# Ease_buck_regulator_v2.net
KiCad netlist of a schematic drawn in EasyEDA Pro
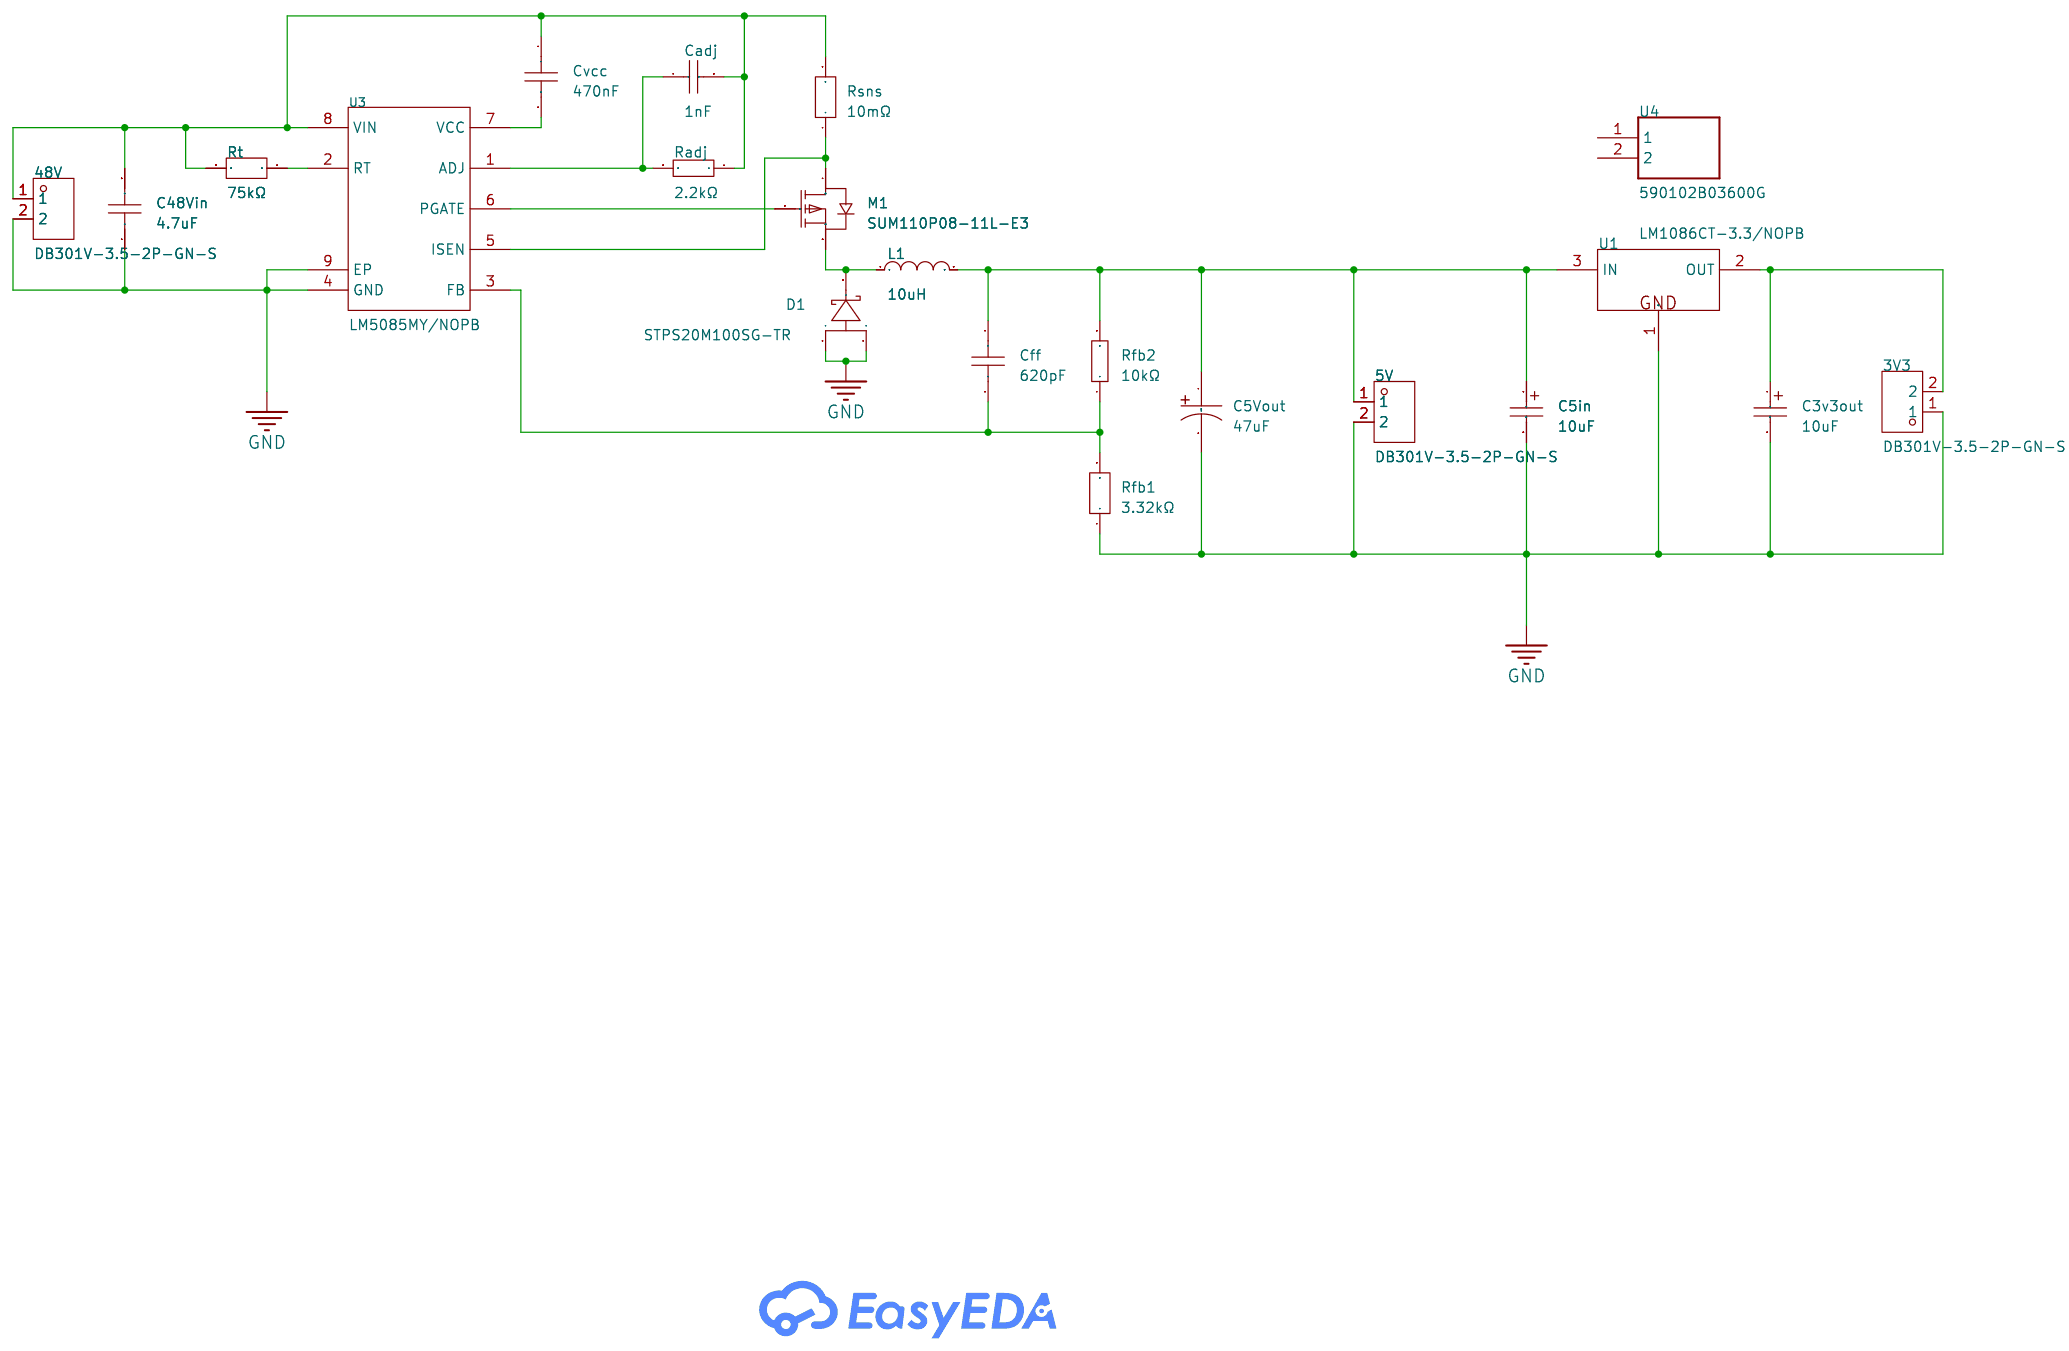
[diagram p0: schematic sheet]

(export (version "E")
  (design (tool "Eeschema 10.0.6"))
  (components
    (comp (ref "3V3")
      (value "DB301V-3.5-2P-GN-S")
      (footprint "easyedapro:CONN-TH_DB301V-3.5-2P-GN")
      (fields (field (name "Manufacturer") "DORABO(地博电气)"))
      (libsource (lib "easyedapro") (part "DB301V-3.5-2P-GN"))
    )
    (comp (ref "5V")
      (value "DB301V-3.5-2P-GN-S")
      (footprint "easyedapro:CONN-TH_DB301V-3.5-2P-GN")
      (fields (field (name "Manufacturer") "DORABO(地博电气)"))
      (libsource (lib "easyedapro") (part "DB301V-3.5-2P-GN"))
    )
    (comp (ref "48V")
      (value "DB301V-3.5-2P-GN-S")
      (footprint "easyedapro:CONN-TH_DB301V-3.5-2P-GN")
      (fields (field (name "Manufacturer") "DORABO(地博电气)"))
      (libsource (lib "easyedapro") (part "DB301V-3.5-2P-GN"))
    )
    (comp (ref "C3v3out")
      (value "10uF")
      (footprint "easyedapro:CASE-A_3216")
      (fields (field (name "Manufacturer Part") "TAJA106M010RNJ") (field (name "Manufacturer") "Kyocera AVX"))
      (libsource (lib "easyedapro") (part "TAJA106M010RNJ"))
    )
    (comp (ref "C5in")
      (value "10uF")
      (footprint "easyedapro:CASE-A_3216")
      (fields (field (name "Manufacturer Part") "TAJA106M010RNJ") (field (name "Manufacturer") "Kyocera AVX"))
      (libsource (lib "easyedapro") (part "TAJA106M010RNJ"))
    )
    (comp (ref "C5Vout")
      (value "47uF")
      (footprint "easyedapro:CAP-SMD_L3.5-W2.8")
      (fields
        (field (name "Manufacturer Part") "TPSB476K010R0250")
        (field (name "Manufacturer") "Kyocera AVX")
      )
      (libsource (lib "easyedapro") (part "TPSB476K010R0250"))
    )
    (comp (ref "C48Vin")
      (value "4.7uF")
      (footprint "easyedapro:C1210")
      (description "Capacitance:4.7uF Tolerance:±10% Tolerance:±10% Voltage Rating:100V Temperature Coefficient:X7S")
      (fields
        (field (name "Manufacturer Part") "GCM32DC72A475KE02L")
        (field (name "Manufacturer") "muRata(村田)")
      )
      (libsource (lib "easyedapro") (part "GCM32DC72A475KE02L"))
    )
    (comp (ref "Cadj")
      (value "1nF")
      (footprint "easyedapro:C0805")
      (description "Capacitance:1nF Tolerance:±5% Tolerance:±5% Voltage Rating:50V Temperature Coefficient:C0G")
      (fields
        (field (name "Manufacturer Part") "CL21C102JBCNNNC")
        (field (name "Manufacturer") "SAMSUNG(三星)")
      )
      (libsource (lib "easyedapro") (part "CL21C102JBCNNNC"))
    )
    (comp (ref "Cff")
      (value "620pF")
      (footprint "easyedapro:C0805")
      (fields
        (field (name "Manufacturer Part") "CL21C621JBCNNNC")
        (field (name "Manufacturer") "SAMSUNG(三星)")
      )
      (libsource (lib "easyedapro") (part "CL21C621JBCNNNC"))
    )
    (comp (ref "Cvcc")
      (value "470nF")
      (footprint "easyedapro:C0805")
      (fields
        (field (name "Manufacturer Part") "TMK212BJ474KD-T")
        (field (name "Manufacturer") "TAIYO YUDEN(太诱)")
      )
      (libsource (lib "easyedapro") (part "TMK212BJ474KD-T"))
    )
    (comp (ref "D1")
      (value "STPS20M100SG-TR")
      (footprint "easyedapro:D2PAK_L10.4-W8.5-P2.54-LS15.4-BR")
      (fields (field (name "Manufacturer") "ST(意法半导体)"))
      (libsource (lib "easyedapro") (part "STPS20M100SG-TR"))
    )
    (comp (ref "L1")
      (value "10uH")
      (footprint "easyedapro:IND-SMD_L13.9-W13.5")
      (fields (field (name "Manufacturer Part") "SRP1250-100M") (field (name "Manufacturer") "BOURNS"))
      (libsource (lib "easyedapro") (part "SRP1250-100M"))
    )
    (comp (ref "M1")
      (value "SUM110P08-11L-E3")
      (footprint "easyedapro:TO-263-2_L10.0-W9.1-P5.08-LS15.2-BL-2")
      (fields (field (name "Manufacturer") "VISHAY(威世)"))
      (libsource (lib "easyedapro") (part "SUM110P08-11L-E3"))
    )
    (comp (ref "Radj")
      (value "2.2kΩ")
      (footprint "easyedapro:R0603")
      (fields (field (name "Manufacturer Part") "RC0603FR-072K2L") (field (name "Manufacturer") "YAGEO(国巨)"))
      (libsource (lib "easyedapro") (part "RC0603FR-072K2L"))
    )
    (comp (ref "Rfb1")
      (value "3.32kΩ")
      (footprint "easyedapro:R0402")
      (fields
        (field (name "Manufacturer Part") "CRCW04023K32FKED")
        (field (name "Manufacturer") "VISHAY(威世)")
      )
      (libsource (lib "easyedapro") (part "CRCW04023K32FKED"))
    )
    (comp (ref "Rfb2")
      (value "10kΩ")
      (footprint "easyedapro:R0402")
      (fields
        (field (name "Manufacturer Part") "CRCW040210K0FKED")
        (field (name "Manufacturer") "VISHAY(威世)")
      )
      (libsource (lib "easyedapro") (part "CRCW040210K0FKED"))
    )
    (comp (ref "Rsns")
      (value "10mΩ")
      (footprint "easyedapro:R1206")
      (fields
        (field (name "Manufacturer Part") "WSLP1206R0100FEA")
        (field (name "Manufacturer") "VISHAY(威世)")
      )
      (libsource (lib "easyedapro") (part "WSLP1206R0100FEA"))
    )
    (comp (ref "Rt")
      (value "75kΩ")
      (footprint "easyedapro:R0402")
      (fields
        (field (name "Manufacturer Part") "CRCW040275K0FKED")
        (field (name "Manufacturer") "VISHAY(威世)")
      )
      (libsource (lib "easyedapro") (part "CRCW040275K0FKED"))
    )
    (comp (ref "U1")
      (value "LM1086CT-3.3/NOPB")
      (footprint "easyedapro:TO-220-3_L10.0-W4.5-P2.54-L")
      (fields (field (name "Manufacturer") "TI(德州仪器)"))
      (libsource (lib "easyedapro") (part "LM1086CT-3.3/NOPB"))
    )
    (comp (ref "U3")
      (value "LM5085MY/NOPB")
      (footprint "easyedapro:MSOP-8_L3.0-W3.0-P0.65-LS5.0-BL-EP")
      (fields (field (name "Manufacturer") "TI(德州仪器)"))
      (libsource (lib "easyedapro") (part "LM5085MY/NOPB"))
    )
    (comp (ref "U4")
      (value "590102B03600G")
      (footprint "easyedapro:added line")
      (description "heatsink 10 C W")
      (libsource (lib "easyedapro") (part "590102B03600G"))
    )
  )
  (nets
    (net (code "1") (name "GND") (class "Default")
      (node (ref "3V3") (pin "1") (pinfunction "1_1") (pintype "unspecified"))
      (node (ref "48V") (pin "2") (pinfunction "2_2") (pintype "unspecified"))
      (node (ref "5V") (pin "2") (pinfunction "2_2") (pintype "unspecified"))
      (node (ref "C3v3out") (pin "2") (pinfunction "2_2") (pintype "input"))
      (node (ref "C48Vin") (pin "1") (pinfunction "1_1") (pintype "unspecified"))
      (node (ref "C5Vout") (pin "2") (pinfunction "2_2") (pintype "unspecified"))
      (node (ref "C5in") (pin "2") (pinfunction "2_2") (pintype "input"))
      (node (ref "D1") (pin "1") (pinfunction "A_1") (pintype "unspecified"))
      (node (ref "D1") (pin "2") (pinfunction "A_2") (pintype "unspecified"))
      (node (ref "Rfb1") (pin "1") (pinfunction "1_1") (pintype "unspecified"))
      (node (ref "U1") (pin "1") (pinfunction "GND_1") (pintype "unspecified"))
      (node (ref "U3") (pin "4") (pinfunction "GND_4") (pintype "input"))
      (node (ref "U3") (pin "9") (pinfunction "EP_9") (pintype "input"))
    )
    (net (code "2") (name "Net-(D1-K)") (class "Default")
      (node (ref "D1") (pin "3") (pinfunction "K_3") (pintype "unspecified"))
      (node (ref "L1") (pin "1") (pinfunction "1_1") (pintype "unspecified"))
      (node (ref "M1") (pin "3") (pinfunction "S_3") (pintype "unspecified"))
    )
    (net (code "3") (name "Net-(M1-D)") (class "Default")
      (node (ref "M1") (pin "4") (pinfunction "D_4") (pintype "unspecified"))
      (node (ref "Rsns") (pin "1") (pinfunction "1_1") (pintype "unspecified"))
      (node (ref "U3") (pin "5") (pinfunction "ISEN_5") (pintype "input"))
    )
    (net (code "4") (name "Net-(M1-G)") (class "Default")
      (node (ref "M1") (pin "1") (pinfunction "G_1") (pintype "unspecified"))
      (node (ref "U3") (pin "6") (pinfunction "PGATE_6") (pintype "input"))
    )
    (net (code "5") (name "Net-(U1-IN)") (class "Default")
      (node (ref "5V") (pin "1") (pinfunction "1_1") (pintype "unspecified"))
      (node (ref "C5Vout") (pin "1") (pinfunction "1_1") (pintype "unspecified"))
      (node (ref "C5in") (pin "1") (pinfunction "1_1") (pintype "input"))
      (node (ref "Cff") (pin "1") (pinfunction "1_1") (pintype "unspecified"))
      (node (ref "L1") (pin "2") (pinfunction "2_2") (pintype "unspecified"))
      (node (ref "Rfb2") (pin "2") (pinfunction "2_2") (pintype "unspecified"))
      (node (ref "U1") (pin "3") (pinfunction "IN_3") (pintype "unspecified"))
    )
    (net (code "6") (name "Net-(U1-OUT)") (class "Default")
      (node (ref "3V3") (pin "2") (pinfunction "2_2") (pintype "unspecified"))
      (node (ref "C3v3out") (pin "1") (pinfunction "1_1") (pintype "input"))
      (node (ref "U1") (pin "2") (pinfunction "OUT_2") (pintype "unspecified"))
    )
    (net (code "7") (name "Net-(U3-ADJ)") (class "Default")
      (node (ref "Cadj") (pin "1") (pinfunction "1_1") (pintype "input"))
      (node (ref "Radj") (pin "2") (pinfunction "2_2") (pintype "input"))
      (node (ref "U3") (pin "1") (pinfunction "ADJ_1") (pintype "input"))
    )
    (net (code "8") (name "Net-(U3-FB)") (class "Default")
      (node (ref "Cff") (pin "2") (pinfunction "2_2") (pintype "unspecified"))
      (node (ref "Rfb1") (pin "2") (pinfunction "2_2") (pintype "unspecified"))
      (node (ref "Rfb2") (pin "1") (pinfunction "1_1") (pintype "unspecified"))
      (node (ref "U3") (pin "3") (pinfunction "FB_3") (pintype "input"))
    )
    (net (code "9") (name "Net-(U3-RT)") (class "Default")
      (node (ref "Rt") (pin "1") (pinfunction "1_1") (pintype "unspecified"))
      (node (ref "U3") (pin "2") (pinfunction "RT_2") (pintype "input"))
    )
    (net (code "10") (name "Net-(U3-VCC)") (class "Default")
      (node (ref "Cvcc") (pin "2") (pinfunction "2_2") (pintype "unspecified"))
      (node (ref "U3") (pin "7") (pinfunction "VCC_7") (pintype "input"))
    )
    (net (code "11") (name "Net-(U3-VIN)") (class "Default")
      (node (ref "48V") (pin "1") (pinfunction "1_1") (pintype "unspecified"))
      (node (ref "C48Vin") (pin "2") (pinfunction "2_2") (pintype "unspecified"))
      (node (ref "Cadj") (pin "2") (pinfunction "2_2") (pintype "input"))
      (node (ref "Cvcc") (pin "1") (pinfunction "1_1") (pintype "unspecified"))
      (node (ref "Radj") (pin "1") (pinfunction "1_1") (pintype "input"))
      (node (ref "Rsns") (pin "2") (pinfunction "2_2") (pintype "unspecified"))
      (node (ref "Rt") (pin "2") (pinfunction "2_2") (pintype "unspecified"))
      (node (ref "U3") (pin "8") (pinfunction "VIN_8") (pintype "input"))
    )
    (net (code "12") (name "unconnected-(U4-Pad1)") (class "Default")
      (node (ref "U4") (pin "1") (pinfunction "1_1") (pintype "bidirectional"))
    )
    (net (code "13") (name "unconnected-(U4-Pad2)") (class "Default")
      (node (ref "U4") (pin "2") (pinfunction "2_2") (pintype "bidirectional"))
    )
  )
)
